# USB.net
KiCad netlist of a schematic drawn in Altium Designer
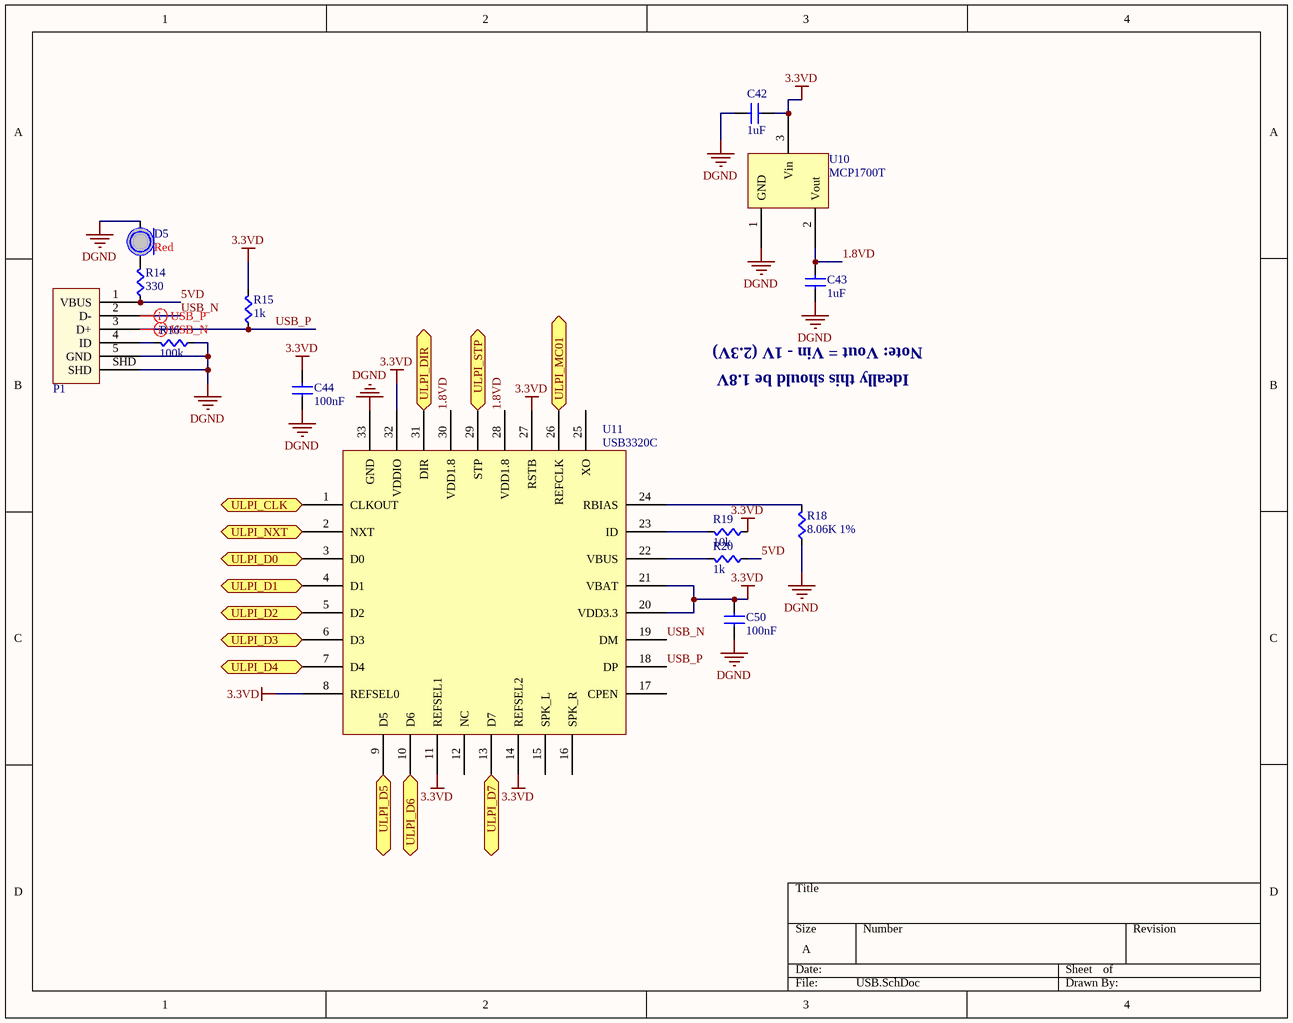
[diagram p0: USB.SchDoc]

(export (version "E")
  (design (tool "Eeschema 10.0.6"))
  (components
    (comp (ref "C42")
      (value "1uF")
      (footprint "CAPC0603")
      (fields (field (name "Comment") "Cap"))
      (libsource (lib "SubjuGator8") (part "Cap"))
    )
    (comp (ref "C43")
      (value "1uF")
      (footprint "CAPC0603")
      (fields (field (name "Comment") "Cap"))
      (libsource (lib "SubjuGator8") (part "Cap"))
    )
    (comp (ref "C44")
      (value "100nF")
      (footprint "CAPC0603")
      (fields (field (name "Comment") "Cap"))
      (libsource (lib "SubjuGator8") (part "Cap"))
    )
    (comp (ref "C50")
      (value "100nF")
      (footprint "CAPC0603")
      (fields (field (name "Comment") "Cap"))
      (libsource (lib "SubjuGator8") (part "Cap"))
    )
    (comp (ref "D5")
      (value "LED")
      (footprint "LED0805")
      (fields (field (name "COLOR") "Red"))
      (libsource (lib "Semiconductors") (part "LED"))
    )
    (comp (ref "P1")
      (value "USB Micro")
      (footprint "10118192-0001LF")
      (description "USB Mini B Metal Shield SMT")
      (libsource (lib "SubjuGator8") (part "USB Micro"))
    )
    (comp (ref "R14")
      (value "330")
      (footprint "RES0603")
      (fields (field (name "Comment") "Res"))
      (libsource (lib "Passives") (part "Res"))
    )
    (comp (ref "R15")
      (value "1k")
      (footprint "RES0603")
      (fields (field (name "Comment") "Res"))
      (libsource (lib "Passives") (part "Res"))
    )
    (comp (ref "R16")
      (value "100k")
      (footprint "RES0603")
      (fields (field (name "Comment") "Res"))
      (libsource (lib "Passives") (part "Res"))
    )
    (comp (ref "R18")
      (value "8.06K 1%")
      (footprint "RES0603")
      (fields (field (name "Comment") "Res"))
      (libsource (lib "Passives") (part "Res"))
    )
    (comp (ref "R19")
      (value "10k")
      (footprint "RES0603")
      (fields (field (name "Comment") "Res"))
      (libsource (lib "Passives") (part "Res"))
    )
    (comp (ref "R20")
      (value "1k")
      (footprint "RES0603")
      (fields (field (name "Comment") "Res"))
      (libsource (lib "Passives") (part "Res"))
    )
    (comp (ref "U10")
      (value "MCP1700T")
      (footprint "SOT23-3")
      (description "IC REG LDO 1.8V 0.2A SOT23-3")
      (libsource (lib "SubjuGator8") (part "LDO 1.8V"))
    )
    (comp (ref "U11")
      (value "USB3320C")
      (footprint "QFN-32")
      (description "MULTI-FREQ USB 2.0 ULPI PHY")
      (libsource (lib "ICs") (part "USB3320C"))
    )
  )
  (nets
    (net (code "1") (name "/1.8VD") (class "Default")
      (node (ref "C43") (pin "1") (pinfunction "A_1") (pintype "passive"))
      (node (ref "U10") (pin "2") (pinfunction "Vout_2") (pintype "passive"))
      (node (ref "U11") (pin "28") (pinfunction "VDD1.8_28") (pintype "passive"))
      (node (ref "U11") (pin "30") (pinfunction "VDD1.8_30") (pintype "passive"))
    )
    (net (code "2") (name "/5VD") (class "Default")
      (node (ref "P1") (pin "1") (pinfunction "VBUS_1") (pintype "passive"))
      (node (ref "R14") (pin "2") (pinfunction "B_2") (pintype "passive"))
      (node (ref "R20") (pin "2") (pinfunction "B_2") (pintype "passive"))
    )
    (net (code "3") (name "/ULPI_CLK") (class "Default")
      (node (ref "U11") (pin "1") (pinfunction "CLKOUT_1") (pintype "passive"))
    )
    (net (code "4") (name "/ULPI_D0") (class "Default")
      (node (ref "U11") (pin "3") (pinfunction "D0_3") (pintype "passive"))
    )
    (net (code "5") (name "/ULPI_D1") (class "Default")
      (node (ref "U11") (pin "4") (pinfunction "D1_4") (pintype "passive"))
    )
    (net (code "6") (name "/ULPI_D2") (class "Default")
      (node (ref "U11") (pin "5") (pinfunction "D2_5") (pintype "passive"))
    )
    (net (code "7") (name "/ULPI_D3") (class "Default")
      (node (ref "U11") (pin "6") (pinfunction "D3_6") (pintype "passive"))
    )
    (net (code "8") (name "/ULPI_D4") (class "Default")
      (node (ref "U11") (pin "7") (pinfunction "D4_7") (pintype "passive"))
    )
    (net (code "9") (name "/ULPI_D5") (class "Default")
      (node (ref "U11") (pin "9") (pinfunction "D5_9") (pintype "passive"))
    )
    (net (code "10") (name "/ULPI_D6") (class "Default")
      (node (ref "U11") (pin "10") (pinfunction "D6_10") (pintype "passive"))
    )
    (net (code "11") (name "/ULPI_D7") (class "Default")
      (node (ref "U11") (pin "13") (pinfunction "D7_13") (pintype "passive"))
    )
    (net (code "12") (name "/ULPI_DIR") (class "Default")
      (node (ref "U11") (pin "31") (pinfunction "DIR_31") (pintype "passive"))
    )
    (net (code "13") (name "/ULPI_MC01") (class "Default")
      (node (ref "U11") (pin "26") (pinfunction "REFCLK_26") (pintype "passive"))
    )
    (net (code "14") (name "/ULPI_NXT") (class "Default")
      (node (ref "U11") (pin "2") (pinfunction "NXT_2") (pintype "passive"))
    )
    (net (code "15") (name "/ULPI_STP") (class "Default")
      (node (ref "U11") (pin "29") (pinfunction "STP_29") (pintype "passive"))
    )
    (net (code "16") (name "/USB_N") (class "Default")
      (node (ref "P1") (pin "2") (pinfunction "D-_2") (pintype "passive"))
      (node (ref "U11") (pin "19") (pinfunction "DM_19") (pintype "passive"))
    )
    (net (code "17") (name "/USB_P") (class "Default")
      (node (ref "P1") (pin "3") (pinfunction "D+_3") (pintype "passive"))
      (node (ref "R15") (pin "2") (pinfunction "B_2") (pintype "passive"))
      (node (ref "U11") (pin "18") (pinfunction "DP_18") (pintype "passive"))
    )
    (net (code "18") (name "3.3VD") (class "Default")
      (node (ref "C42") (pin "1") (pinfunction "A_1") (pintype "passive"))
      (node (ref "C44") (pin "1") (pinfunction "A_1") (pintype "passive"))
      (node (ref "C50") (pin "1") (pinfunction "A_1") (pintype "passive"))
      (node (ref "R15") (pin "1") (pinfunction "A_1") (pintype "passive"))
      (node (ref "R19") (pin "2") (pinfunction "B_2") (pintype "passive"))
      (node (ref "U10") (pin "3") (pinfunction "Vin_3") (pintype "passive"))
      (node (ref "U11") (pin "11") (pinfunction "REFSEL1_11") (pintype "passive"))
      (node (ref "U11") (pin "14") (pinfunction "REFSEL2_14") (pintype "passive"))
      (node (ref "U11") (pin "20") (pinfunction "VDD3.3_20") (pintype "passive"))
      (node (ref "U11") (pin "21") (pinfunction "VBAT_21") (pintype "passive"))
      (node (ref "U11") (pin "27") (pinfunction "RSTB_27") (pintype "passive"))
      (node (ref "U11") (pin "32") (pinfunction "VDDIO_32") (pintype "passive"))
      (node (ref "U11") (pin "8") (pinfunction "REFSEL0_8") (pintype "passive"))
    )
    (net (code "19") (name "DGND") (class "Default")
      (node (ref "C42") (pin "2") (pinfunction "B_2") (pintype "passive"))
      (node (ref "C43") (pin "2") (pinfunction "B_2") (pintype "passive"))
      (node (ref "C44") (pin "2") (pinfunction "B_2") (pintype "passive"))
      (node (ref "C50") (pin "2") (pinfunction "B_2") (pintype "passive"))
      (node (ref "D5") (pin "C") (pinfunction "C_C") (pintype "passive"))
      (node (ref "P1") (pin "5") (pinfunction "GND_5") (pintype "passive"))
      (node (ref "P1") (pin "SHD") (pinfunction "SHD_SHD") (pintype "passive"))
      (node (ref "R16") (pin "2") (pinfunction "B_2") (pintype "passive"))
      (node (ref "R18") (pin "2") (pinfunction "B_2") (pintype "passive"))
      (node (ref "U10") (pin "1") (pinfunction "GND_1") (pintype "passive"))
      (node (ref "U11") (pin "33") (pinfunction "GND_33") (pintype "passive"))
    )
    (net (code "20") (name "Net-(P1-ID)") (class "Default")
      (node (ref "P1") (pin "4") (pinfunction "ID_4") (pintype "passive"))
      (node (ref "R16") (pin "1") (pinfunction "A_1") (pintype "passive"))
    )
    (net (code "21") (name "Net-(R14-A)") (class "Default")
      (node (ref "D5") (pin "A") (pinfunction "A_A") (pintype "passive"))
      (node (ref "R14") (pin "1") (pinfunction "A_1") (pintype "passive"))
    )
    (net (code "22") (name "Net-(R18-A)") (class "Default")
      (node (ref "R18") (pin "1") (pinfunction "A_1") (pintype "passive"))
      (node (ref "U11") (pin "24") (pinfunction "RBIAS_24") (pintype "passive"))
    )
    (net (code "23") (name "Net-(R19-A)") (class "Default")
      (node (ref "R19") (pin "1") (pinfunction "A_1") (pintype "passive"))
      (node (ref "U11") (pin "23") (pinfunction "ID_23") (pintype "passive"))
    )
    (net (code "24") (name "Net-(R20-A)") (class "Default")
      (node (ref "R20") (pin "1") (pinfunction "A_1") (pintype "passive"))
      (node (ref "U11") (pin "22") (pinfunction "VBUS_22") (pintype "passive"))
    )
    (net (code "25") (name "unconnected-(U11-CPEN-Pad17)") (class "Default")
      (node (ref "U11") (pin "17") (pinfunction "CPEN_17") (pintype "passive"))
    )
    (net (code "26") (name "unconnected-(U11-NC-Pad12)") (class "Default")
      (node (ref "U11") (pin "12") (pinfunction "NC_12") (pintype "passive"))
    )
    (net (code "27") (name "unconnected-(U11-SPK_L-Pad15)") (class "Default")
      (node (ref "U11") (pin "15") (pinfunction "SPK_L_15") (pintype "passive"))
    )
    (net (code "28") (name "unconnected-(U11-SPK_R-Pad16)") (class "Default")
      (node (ref "U11") (pin "16") (pinfunction "SPK_R_16") (pintype "passive"))
    )
    (net (code "29") (name "unconnected-(U11-XO-Pad25)") (class "Default")
      (node (ref "U11") (pin "25") (pinfunction "XO_25") (pintype "passive"))
    )
  )
)
